# Boost2.net
KiCad netlist of a schematic drawn in Altium Designer
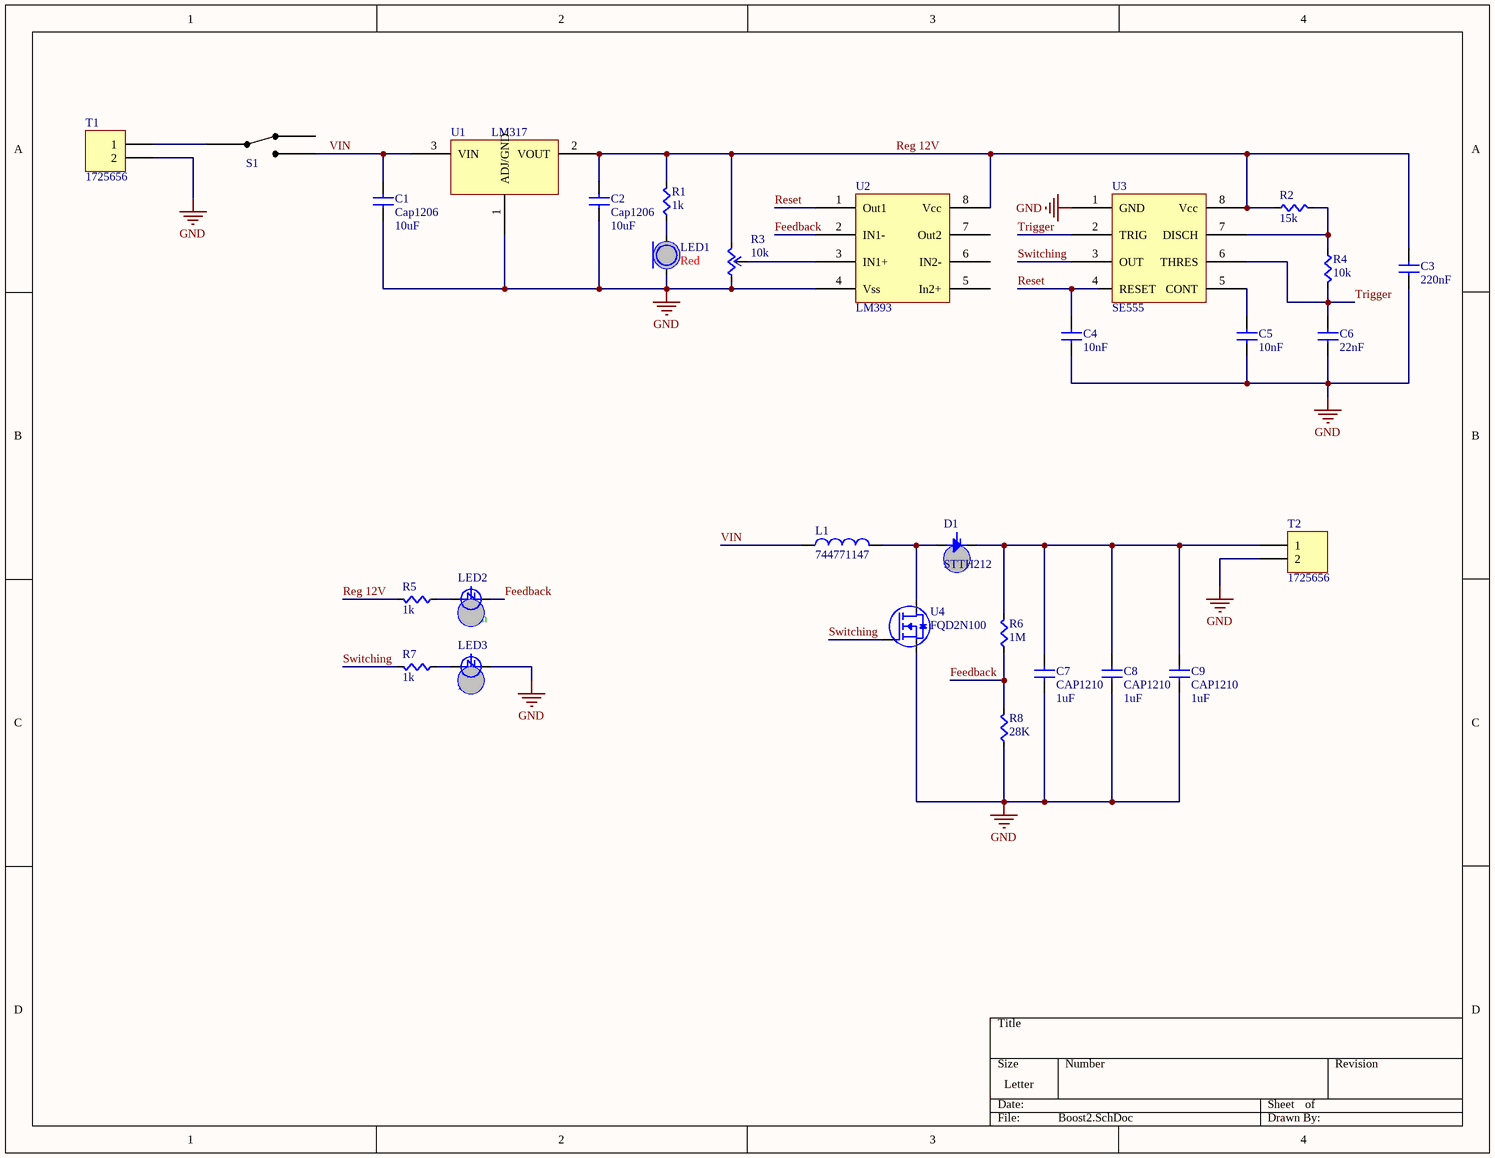
[diagram p0: Boost2.SchDoc]

(export (version "E")
  (design (tool "Eeschema 10.0.6"))
  (components
    (comp (ref "C1")
      (value "Cap1206")
      (footprint "CAP1206")
      (description "CAP CER 1UF 50V 10% X7R 1206")
      (fields (field (name "ALTIUM_VALUE") "10uF"))
      (libsource (lib "Passives") (part "Cap1206"))
    )
    (comp (ref "C2")
      (value "Cap1206")
      (footprint "CAP1206")
      (description "CAP CER 1UF 50V 10% X7R 1206")
      (fields (field (name "ALTIUM_VALUE") "10uF"))
      (libsource (lib "Passives") (part "Cap1206"))
    )
    (comp (ref "C3")
      (value "220nF")
      (footprint "CAPC0603")
      (fields (field (name "Comment") "Cap"))
      (libsource (lib "Passives") (part "Cap"))
    )
    (comp (ref "C4")
      (value "10nF")
      (footprint "CAPC0603")
      (fields (field (name "Comment") "Cap"))
      (libsource (lib "Passives") (part "Cap"))
    )
    (comp (ref "C5")
      (value "10nF")
      (footprint "CAPC0603")
      (fields (field (name "Comment") "Cap"))
      (libsource (lib "Passives") (part "Cap"))
    )
    (comp (ref "C6")
      (value "22nF")
      (footprint "CAPC0603")
      (fields (field (name "Comment") "Cap"))
      (libsource (lib "Passives") (part "Cap"))
    )
    (comp (ref "C7")
      (value "CAP1210")
      (footprint "CAP1210")
      (description "CAP CER 10UF 50V 20% X5R 1210")
      (fields (field (name "ALTIUM_VALUE") "1uF"))
      (libsource (lib "Passives") (part "CAP1210"))
    )
    (comp (ref "C8")
      (value "CAP1210")
      (footprint "CAP1210")
      (description "CAP CER 10UF 50V 20% X5R 1210")
      (fields (field (name "ALTIUM_VALUE") "1uF"))
      (libsource (lib "Passives") (part "CAP1210"))
    )
    (comp (ref "C9")
      (value "CAP1210")
      (footprint "CAP1210")
      (description "CAP CER 10UF 50V 20% X5R 1210")
      (fields (field (name "ALTIUM_VALUE") "1uF"))
      (libsource (lib "Passives") (part "CAP1210"))
    )
    (comp (ref "D1")
      (value "STTH212")
      (footprint "STTH212")
      (description "DIODE GEN PURP 1.2KV 2A SMB")
      (libsource (lib "Sonar_Library") (part "STTH212"))
    )
    (comp (ref "L1")
      (value "744771147")
      (footprint "744771147")
      (description "FIXED IND 47UH 2.21A 75 MOHM SMD")
      (libsource (lib "Sonar_Library") (part "744771147"))
    )
    (comp (ref "LED1")
      (value "LED")
      (footprint "LED0603")
      (fields (field (name "COLOR") "Red"))
      (libsource (lib "") (part "LED_1"))
    )
    (comp (ref "LED2")
      (value "LED")
      (footprint "LED0603")
      (fields (field (name "COLOR") "Green"))
      (libsource (lib "Semiconductors") (part "LED"))
    )
    (comp (ref "LED3")
      (value "LED")
      (footprint "LED0603")
      (fields (field (name "COLOR") "Blue"))
      (libsource (lib "Semiconductors") (part "LED"))
    )
    (comp (ref "R1")
      (value "1k")
      (footprint "RES0603")
      (fields (field (name "Comment") "Res"))
      (libsource (lib "Passives") (part "Res"))
    )
    (comp (ref "R2")
      (value "15k")
      (footprint "RES0603")
      (fields (field (name "Comment") "Res"))
      (libsource (lib "Passives") (part "Res"))
    )
    (comp (ref "R3")
      (value "10k")
      (footprint "ST4ETA103")
      (description "Potentiometer")
      (fields (field (name "Comment") "Pot"))
      (libsource (lib "Passives") (part "Potentiometer"))
    )
    (comp (ref "R4")
      (value "10k")
      (footprint "RES0603")
      (fields (field (name "Comment") "Res"))
      (libsource (lib "Passives") (part "Res"))
    )
    (comp (ref "R5")
      (value "1k")
      (footprint "RES0603")
      (fields (field (name "Comment") "Res"))
      (libsource (lib "Passives") (part "Res"))
    )
    (comp (ref "R6")
      (value "1M")
      (footprint "RES0603")
      (fields (field (name "Comment") "Res"))
      (libsource (lib "Passives") (part "Res"))
    )
    (comp (ref "R7")
      (value "1k")
      (footprint "RES0603")
      (fields (field (name "Comment") "Res"))
      (libsource (lib "Passives") (part "Res"))
    )
    (comp (ref "R8")
      (value "28K")
      (footprint "RES0805")
      (fields (field (name "Comment") "Res"))
      (libsource (lib "Passives") (part "Res"))
    )
    (comp (ref "S1")
      (value "SPDT Slide Switch")
      (footprint "CL-SB-12B-01T")
      (libsource (lib "Passives") (part "SPDT Slide Switch"))
    )
    (comp (ref "T1")
      (value "1725656")
      (footprint "1725656")
      (description "CONN TERM BLOCK 2.54MM 2POS")
      (libsource (lib "Sonar_Library") (part "1725656"))
    )
    (comp (ref "T2")
      (value "1725656")
      (footprint "1725656")
      (description "CONN TERM BLOCK 2.54MM 2POS")
      (libsource (lib "") (part "1725656_1"))
    )
    (comp (ref "U1")
      (value "LM317")
      (footprint "LM317")
      (description "IC REG LDO ADJ 1.5A SOT223")
      (libsource (lib "Sonar_Library") (part "LM317"))
    )
    (comp (ref "U2")
      (value "LM393")
      (footprint "LM393")
      (description "IC VOLT COMPARATOR DUAL 8MISOIC")
      (libsource (lib "Sonar_Library") (part "LM393"))
    )
    (comp (ref "U3")
      (value "SE555")
      (footprint "SE555")
      (description "IC OSC SGL TIMER 100KHZ 8SOIC")
      (libsource (lib "Sonar_Library") (part "SE555"))
    )
    (comp (ref "U4")
      (value "FQD2N100")
      (footprint "FQD2N100")
      (description "MOSFET N-CH 1000V 1.6A DPAK")
      (libsource (lib "Sonar_Library") (part "FQD2N100"))
    )
  )
  (nets
    (net (code "1") (name "/Feedback") (class "Default")
      (node (ref "LED2") (pin "C") (pinfunction "C_C") (pintype "passive"))
      (node (ref "R6") (pin "2") (pinfunction "B_2") (pintype "passive"))
      (node (ref "R8") (pin "1") (pinfunction "A_1") (pintype "passive"))
      (node (ref "U2") (pin "2") (pinfunction "IN1-_2") (pintype "passive"))
    )
    (net (code "2") (name "/Reg 12V") (class "Default")
      (node (ref "C2") (pin "1") (pinfunction "A_1") (pintype "passive"))
      (node (ref "C3") (pin "1") (pinfunction "A_1") (pintype "passive"))
      (node (ref "R1") (pin "1") (pinfunction "A_1") (pintype "passive"))
      (node (ref "R2") (pin "2") (pinfunction "B_2") (pintype "passive"))
      (node (ref "R3") (pin "1") (pinfunction "1_1") (pintype "passive"))
      (node (ref "R5") (pin "1") (pinfunction "A_1") (pintype "passive"))
      (node (ref "U1") (pin "2") (pinfunction "VOUT_2") (pintype "passive"))
      (node (ref "U2") (pin "8") (pinfunction "Vcc_8") (pintype "passive"))
      (node (ref "U3") (pin "8") (pinfunction "Vcc_8") (pintype "passive"))
    )
    (net (code "3") (name "/Reset") (class "Default")
      (node (ref "C4") (pin "2") (pinfunction "B_2") (pintype "passive"))
      (node (ref "U2") (pin "1") (pinfunction "Out1_1") (pintype "passive"))
      (node (ref "U3") (pin "4") (pinfunction "RESET_4") (pintype "passive"))
    )
    (net (code "4") (name "/Switching") (class "Default")
      (node (ref "R7") (pin "1") (pinfunction "A_1") (pintype "passive"))
      (node (ref "U3") (pin "3") (pinfunction "OUT_3") (pintype "passive"))
      (node (ref "U4") (pin "G") (pinfunction "G_G") (pintype "passive"))
    )
    (net (code "5") (name "/Trigger") (class "Default")
      (node (ref "C6") (pin "1") (pinfunction "A_1") (pintype "passive"))
      (node (ref "R4") (pin "1") (pinfunction "A_1") (pintype "passive"))
      (node (ref "U3") (pin "2") (pinfunction "TRIG_2") (pintype "passive"))
      (node (ref "U3") (pin "6") (pinfunction "THRES_6") (pintype "passive"))
    )
    (net (code "6") (name "/VIN") (class "Default")
      (node (ref "C1") (pin "1") (pinfunction "A_1") (pintype "passive"))
      (node (ref "L1") (pin "1") (pinfunction "A_1") (pintype "passive"))
      (node (ref "S1") (pin "3") (pinfunction "3_3") (pintype "passive"))
      (node (ref "U1") (pin "3") (pinfunction "VIN_3") (pintype "passive"))
    )
    (net (code "7") (name "GND") (class "Default")
      (node (ref "C1") (pin "2") (pinfunction "B_2") (pintype "passive"))
      (node (ref "C2") (pin "2") (pinfunction "B_2") (pintype "passive"))
      (node (ref "C3") (pin "2") (pinfunction "B_2") (pintype "passive"))
      (node (ref "C4") (pin "1") (pinfunction "A_1") (pintype "passive"))
      (node (ref "C5") (pin "2") (pinfunction "B_2") (pintype "passive"))
      (node (ref "C6") (pin "2") (pinfunction "B_2") (pintype "passive"))
      (node (ref "C7") (pin "2") (pinfunction "B_2") (pintype "passive"))
      (node (ref "C8") (pin "2") (pinfunction "B_2") (pintype "passive"))
      (node (ref "C9") (pin "2") (pinfunction "B_2") (pintype "passive"))
      (node (ref "LED1") (pin "C") (pinfunction "C_C") (pintype "passive"))
      (node (ref "LED3") (pin "C") (pinfunction "C_C") (pintype "passive"))
      (node (ref "R3") (pin "2") (pinfunction "2_2") (pintype "passive"))
      (node (ref "R8") (pin "2") (pinfunction "B_2") (pintype "passive"))
      (node (ref "T1") (pin "2") (pinfunction "2_2") (pintype "passive"))
      (node (ref "T2") (pin "2") (pinfunction "2_2") (pintype "passive"))
      (node (ref "U1") (pin "1") (pinfunction "ADJ/GND_1") (pintype "passive"))
      (node (ref "U2") (pin "4") (pinfunction "Vss_4") (pintype "passive"))
      (node (ref "U3") (pin "1") (pinfunction "GND_1") (pintype "passive"))
      (node (ref "U4") (pin "S") (pinfunction "S_S") (pintype "passive"))
    )
    (net (code "8") (name "Net-(C5-A)") (class "Default")
      (node (ref "C5") (pin "1") (pinfunction "A_1") (pintype "passive"))
      (node (ref "U3") (pin "5") (pinfunction "CONT_5") (pintype "passive"))
    )
    (net (code "9") (name "Net-(C7-A)") (class "Default")
      (node (ref "C7") (pin "1") (pinfunction "A_1") (pintype "passive"))
      (node (ref "C8") (pin "1") (pinfunction "A_1") (pintype "passive"))
      (node (ref "C9") (pin "1") (pinfunction "A_1") (pintype "passive"))
      (node (ref "D1") (pin "C") (pinfunction "C_C") (pintype "passive"))
      (node (ref "R6") (pin "1") (pinfunction "A_1") (pintype "passive"))
      (node (ref "T2") (pin "1") (pinfunction "1_1") (pintype "passive"))
    )
    (net (code "10") (name "Net-(L1-B)") (class "Default")
      (node (ref "D1") (pin "A") (pinfunction "A_A") (pintype "passive"))
      (node (ref "L1") (pin "2") (pinfunction "B_2") (pintype "passive"))
      (node (ref "U4") (pin "D") (pinfunction "D_D") (pintype "passive"))
    )
    (net (code "11") (name "Net-(R1-B)") (class "Default")
      (node (ref "LED1") (pin "A") (pinfunction "A_A") (pintype "passive"))
      (node (ref "R1") (pin "2") (pinfunction "B_2") (pintype "passive"))
    )
    (net (code "12") (name "Net-(R2-A)") (class "Default")
      (node (ref "R2") (pin "1") (pinfunction "A_1") (pintype "passive"))
      (node (ref "R4") (pin "2") (pinfunction "B_2") (pintype "passive"))
      (node (ref "U3") (pin "7") (pinfunction "DISCH_7") (pintype "passive"))
    )
    (net (code "13") (name "Net-(R5-B)") (class "Default")
      (node (ref "LED2") (pin "A") (pinfunction "A_A") (pintype "passive"))
      (node (ref "R5") (pin "2") (pinfunction "B_2") (pintype "passive"))
    )
    (net (code "14") (name "Net-(R7-B)") (class "Default")
      (node (ref "LED3") (pin "A") (pinfunction "A_A") (pintype "passive"))
      (node (ref "R7") (pin "2") (pinfunction "B_2") (pintype "passive"))
    )
    (net (code "15") (name "Net-(S1-Pad2)") (class "Default")
      (node (ref "S1") (pin "2") (pinfunction "2_2") (pintype "passive"))
      (node (ref "T1") (pin "1") (pinfunction "1_1") (pintype "passive"))
    )
    (net (code "16") (name "Net-(U2-IN1+)") (class "Default")
      (node (ref "R3") (pin "3") (pinfunction "3_3") (pintype "passive"))
      (node (ref "U2") (pin "3") (pinfunction "IN1+_3") (pintype "passive"))
    )
    (net (code "17") (name "unconnected-(S1-Pad1)") (class "Default")
      (node (ref "S1") (pin "1") (pinfunction "1_1") (pintype "passive"))
    )
    (net (code "18") (name "unconnected-(U2-IN2--Pad6)") (class "Default")
      (node (ref "U2") (pin "6") (pinfunction "IN2-_6") (pintype "passive"))
    )
    (net (code "19") (name "unconnected-(U2-In2+-Pad5)") (class "Default")
      (node (ref "U2") (pin "5") (pinfunction "In2+_5") (pintype "passive"))
    )
    (net (code "20") (name "unconnected-(U2-Out2-Pad7)") (class "Default")
      (node (ref "U2") (pin "7") (pinfunction "Out2_7") (pintype "passive"))
    )
  )
)
